# module_HC05.net
KiCad netlist of a schematic drawn in EAGLE
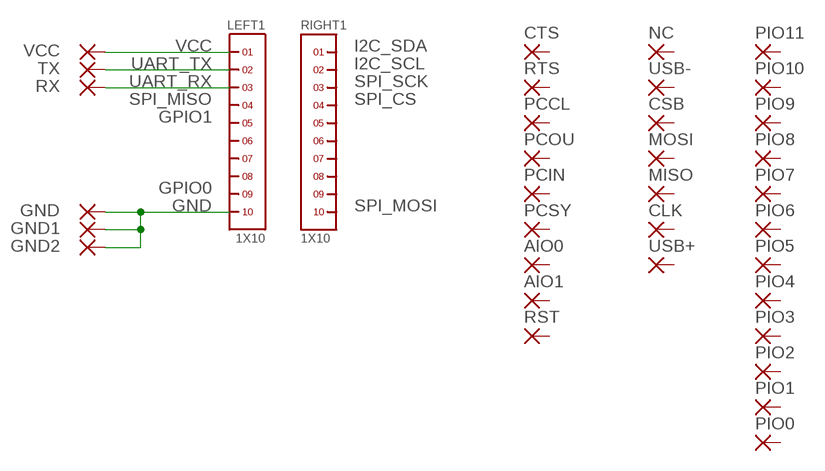
[diagram p0: schematic, sheet 1]

(export (version "E")
  (design (tool "Eeschema 10.0.6"))
  (components
    (comp (ref "AIO0")
      (value "SMD1")
      (footprint "eagle-import:SMD0,65-1,27")
      (libsource (lib "eagle-import") (part "SMD1"))
    )
    (comp (ref "AIO1")
      (value "SMD1")
      (footprint "eagle-import:SMD0,65-1,27")
      (libsource (lib "eagle-import") (part "SMD1"))
    )
    (comp (ref "CLK")
      (value "SMD1")
      (footprint "eagle-import:SMD0,65-1,27")
      (libsource (lib "eagle-import") (part "SMD1"))
    )
    (comp (ref "CSB")
      (value "SMD1")
      (footprint "eagle-import:SMD0,65-1,27")
      (libsource (lib "eagle-import") (part "SMD1"))
    )
    (comp (ref "CTS")
      (value "SMD1")
      (footprint "eagle-import:SMD0,65-1,27")
      (libsource (lib "eagle-import") (part "SMD1"))
    )
    (comp (ref "GND")
      (value "SMD1")
      (footprint "eagle-import:SMD0,65-1,27")
      (libsource (lib "eagle-import") (part "SMD1"))
    )
    (comp (ref "GND1")
      (value "SMD1")
      (footprint "eagle-import:SMD0,65-1,27")
      (libsource (lib "eagle-import") (part "SMD1"))
    )
    (comp (ref "GND2")
      (value "SMD1")
      (footprint "eagle-import:SMD0,65-1,27")
      (libsource (lib "eagle-import") (part "SMD1"))
    )
    (comp (ref "LEFT1")
      (value "1X10")
      (footprint "eagle-import:1X10")
      (libsource (lib "eagle-import") (part "1X10"))
    )
    (comp (ref "MISO")
      (value "SMD1")
      (footprint "eagle-import:SMD0,65-1,27")
      (libsource (lib "eagle-import") (part "SMD1"))
    )
    (comp (ref "MOSI")
      (value "SMD1")
      (footprint "eagle-import:SMD0,65-1,27")
      (libsource (lib "eagle-import") (part "SMD1"))
    )
    (comp (ref "NC")
      (value "SMD1")
      (footprint "eagle-import:SMD0,65-1,27")
      (libsource (lib "eagle-import") (part "SMD1"))
    )
    (comp (ref "PCCL")
      (value "SMD1")
      (footprint "eagle-import:SMD0,65-1,27")
      (libsource (lib "eagle-import") (part "SMD1"))
    )
    (comp (ref "PCIN")
      (value "SMD1")
      (footprint "eagle-import:SMD0,65-1,27")
      (libsource (lib "eagle-import") (part "SMD1"))
    )
    (comp (ref "PCOU")
      (value "SMD1")
      (footprint "eagle-import:SMD0,65-1,27")
      (libsource (lib "eagle-import") (part "SMD1"))
    )
    (comp (ref "PCSY")
      (value "SMD1")
      (footprint "eagle-import:SMD0,65-1,27")
      (libsource (lib "eagle-import") (part "SMD1"))
    )
    (comp (ref "PIO0")
      (value "SMD1")
      (footprint "eagle-import:SMD0,65-1,27")
      (libsource (lib "eagle-import") (part "SMD1"))
    )
    (comp (ref "PIO1")
      (value "SMD1")
      (footprint "eagle-import:SMD0,65-1,27")
      (libsource (lib "eagle-import") (part "SMD1"))
    )
    (comp (ref "PIO2")
      (value "SMD1")
      (footprint "eagle-import:SMD0,65-1,27")
      (libsource (lib "eagle-import") (part "SMD1"))
    )
    (comp (ref "PIO3")
      (value "SMD1")
      (footprint "eagle-import:SMD0,65-1,27")
      (libsource (lib "eagle-import") (part "SMD1"))
    )
    (comp (ref "PIO4")
      (value "SMD1")
      (footprint "eagle-import:SMD0,65-1,27")
      (libsource (lib "eagle-import") (part "SMD1"))
    )
    (comp (ref "PIO5")
      (value "SMD1")
      (footprint "eagle-import:SMD0,65-1,27")
      (libsource (lib "eagle-import") (part "SMD1"))
    )
    (comp (ref "PIO6")
      (value "SMD1")
      (footprint "eagle-import:SMD0,65-1,27")
      (libsource (lib "eagle-import") (part "SMD1"))
    )
    (comp (ref "PIO7")
      (value "SMD1")
      (footprint "eagle-import:SMD0,65-1,27")
      (libsource (lib "eagle-import") (part "SMD1"))
    )
    (comp (ref "PIO8")
      (value "SMD1")
      (footprint "eagle-import:SMD0,65-1,27")
      (libsource (lib "eagle-import") (part "SMD1"))
    )
    (comp (ref "PIO9")
      (value "SMD1")
      (footprint "eagle-import:SMD0,65-1,27")
      (libsource (lib "eagle-import") (part "SMD1"))
    )
    (comp (ref "PIO10")
      (value "SMD1")
      (footprint "eagle-import:SMD0,65-1,27")
      (libsource (lib "eagle-import") (part "SMD1"))
    )
    (comp (ref "PIO11")
      (value "SMD1")
      (footprint "eagle-import:SMD0,65-1,27")
      (libsource (lib "eagle-import") (part "SMD1"))
    )
    (comp (ref "RIGHT1")
      (value "1X10")
      (footprint "eagle-import:1X10")
      (libsource (lib "eagle-import") (part "1X10"))
    )
    (comp (ref "RST")
      (value "SMD1")
      (footprint "eagle-import:SMD0,65-1,27")
      (libsource (lib "eagle-import") (part "SMD1"))
    )
    (comp (ref "RTS")
      (value "SMD1")
      (footprint "eagle-import:SMD0,65-1,27")
      (libsource (lib "eagle-import") (part "SMD1"))
    )
    (comp (ref "RX")
      (value "SMD1")
      (footprint "eagle-import:SMD0,65-1,27")
      (libsource (lib "eagle-import") (part "SMD1"))
    )
    (comp (ref "TX")
      (value "SMD1")
      (footprint "eagle-import:SMD0,65-1,27")
      (libsource (lib "eagle-import") (part "SMD1"))
    )
    (comp (ref "USB+")
      (value "SMD1")
      (footprint "eagle-import:SMD0,65-1,27")
      (libsource (lib "eagle-import") (part "SMD1"))
    )
    (comp (ref "USB-")
      (value "SMD1")
      (footprint "eagle-import:SMD0,65-1,27")
      (libsource (lib "eagle-import") (part "SMD1"))
    )
    (comp (ref "VCC")
      (value "SMD1")
      (footprint "eagle-import:SMD0,65-1,27")
      (libsource (lib "eagle-import") (part "SMD1"))
    )
  )
  (nets
    (net (code "1") (name "Net-(GND-P)") (class "Default")
      (node (ref "GND") (pin "1") (pinfunction "P_1") (pintype "passive"))
      (node (ref "GND1") (pin "1") (pinfunction "P_1") (pintype "passive"))
      (node (ref "GND2") (pin "1") (pinfunction "P_1") (pintype "passive"))
      (node (ref "LEFT1") (pin "10") (pinfunction "10_10") (pintype "bidirectional"))
    )
    (net (code "2") (name "Net-(RX-P)") (class "Default")
      (node (ref "LEFT1") (pin "3") (pinfunction "3_3") (pintype "bidirectional"))
      (node (ref "RX") (pin "1") (pinfunction "P_1") (pintype "passive"))
    )
    (net (code "3") (name "Net-(TX-P)") (class "Default")
      (node (ref "LEFT1") (pin "2") (pinfunction "2_2") (pintype "bidirectional"))
      (node (ref "TX") (pin "1") (pinfunction "P_1") (pintype "passive"))
    )
    (net (code "4") (name "Net-(VCC-P)") (class "Default")
      (node (ref "LEFT1") (pin "1") (pinfunction "1_1") (pintype "bidirectional"))
      (node (ref "VCC") (pin "1") (pinfunction "P_1") (pintype "passive"))
    )
    (net (code "5") (name "unconnected-(AIO0-P-Pad1)") (class "Default")
      (node (ref "AIO0") (pin "1") (pinfunction "P_1") (pintype "passive"))
    )
    (net (code "6") (name "unconnected-(AIO1-P-Pad1)") (class "Default")
      (node (ref "AIO1") (pin "1") (pinfunction "P_1") (pintype "passive"))
    )
    (net (code "7") (name "unconnected-(CLK-P-Pad1)") (class "Default")
      (node (ref "CLK") (pin "1") (pinfunction "P_1") (pintype "passive"))
    )
    (net (code "8") (name "unconnected-(CSB-P-Pad1)") (class "Default")
      (node (ref "CSB") (pin "1") (pinfunction "P_1") (pintype "passive"))
    )
    (net (code "9") (name "unconnected-(CTS-P-Pad1)") (class "Default")
      (node (ref "CTS") (pin "1") (pinfunction "P_1") (pintype "passive"))
    )
    (net (code "10") (name "unconnected-(LEFT1-Pad4)") (class "Default")
      (node (ref "LEFT1") (pin "4") (pinfunction "4_4") (pintype "bidirectional"))
    )
    (net (code "11") (name "unconnected-(LEFT1-Pad5)") (class "Default")
      (node (ref "LEFT1") (pin "5") (pinfunction "5_5") (pintype "bidirectional"))
    )
    (net (code "12") (name "unconnected-(LEFT1-Pad6)") (class "Default")
      (node (ref "LEFT1") (pin "6") (pinfunction "6_6") (pintype "bidirectional"))
    )
    (net (code "13") (name "unconnected-(LEFT1-Pad7)") (class "Default")
      (node (ref "LEFT1") (pin "7") (pinfunction "7_7") (pintype "bidirectional"))
    )
    (net (code "14") (name "unconnected-(LEFT1-Pad8)") (class "Default")
      (node (ref "LEFT1") (pin "8") (pinfunction "8_8") (pintype "bidirectional"))
    )
    (net (code "15") (name "unconnected-(LEFT1-Pad9)") (class "Default")
      (node (ref "LEFT1") (pin "9") (pinfunction "9_9") (pintype "bidirectional"))
    )
    (net (code "16") (name "unconnected-(MISO-P-Pad1)") (class "Default")
      (node (ref "MISO") (pin "1") (pinfunction "P_1") (pintype "passive"))
    )
    (net (code "17") (name "unconnected-(MOSI-P-Pad1)") (class "Default")
      (node (ref "MOSI") (pin "1") (pinfunction "P_1") (pintype "passive"))
    )
    (net (code "18") (name "unconnected-(NC-P-Pad1)") (class "Default")
      (node (ref "NC") (pin "1") (pinfunction "P_1") (pintype "passive"))
    )
    (net (code "19") (name "unconnected-(PCCL-P-Pad1)") (class "Default")
      (node (ref "PCCL") (pin "1") (pinfunction "P_1") (pintype "passive"))
    )
    (net (code "20") (name "unconnected-(PCIN-P-Pad1)") (class "Default")
      (node (ref "PCIN") (pin "1") (pinfunction "P_1") (pintype "passive"))
    )
    (net (code "21") (name "unconnected-(PCOU-P-Pad1)") (class "Default")
      (node (ref "PCOU") (pin "1") (pinfunction "P_1") (pintype "passive"))
    )
    (net (code "22") (name "unconnected-(PCSY-P-Pad1)") (class "Default")
      (node (ref "PCSY") (pin "1") (pinfunction "P_1") (pintype "passive"))
    )
    (net (code "23") (name "unconnected-(PIO0-P-Pad1)") (class "Default")
      (node (ref "PIO0") (pin "1") (pinfunction "P_1") (pintype "passive"))
    )
    (net (code "24") (name "unconnected-(PIO1-P-Pad1)") (class "Default")
      (node (ref "PIO1") (pin "1") (pinfunction "P_1") (pintype "passive"))
    )
    (net (code "25") (name "unconnected-(PIO2-P-Pad1)") (class "Default")
      (node (ref "PIO2") (pin "1") (pinfunction "P_1") (pintype "passive"))
    )
    (net (code "26") (name "unconnected-(PIO3-P-Pad1)") (class "Default")
      (node (ref "PIO3") (pin "1") (pinfunction "P_1") (pintype "passive"))
    )
    (net (code "27") (name "unconnected-(PIO4-P-Pad1)") (class "Default")
      (node (ref "PIO4") (pin "1") (pinfunction "P_1") (pintype "passive"))
    )
    (net (code "28") (name "unconnected-(PIO5-P-Pad1)") (class "Default")
      (node (ref "PIO5") (pin "1") (pinfunction "P_1") (pintype "passive"))
    )
    (net (code "29") (name "unconnected-(PIO6-P-Pad1)") (class "Default")
      (node (ref "PIO6") (pin "1") (pinfunction "P_1") (pintype "passive"))
    )
    (net (code "30") (name "unconnected-(PIO7-P-Pad1)") (class "Default")
      (node (ref "PIO7") (pin "1") (pinfunction "P_1") (pintype "passive"))
    )
    (net (code "31") (name "unconnected-(PIO8-P-Pad1)") (class "Default")
      (node (ref "PIO8") (pin "1") (pinfunction "P_1") (pintype "passive"))
    )
    (net (code "32") (name "unconnected-(PIO9-P-Pad1)") (class "Default")
      (node (ref "PIO9") (pin "1") (pinfunction "P_1") (pintype "passive"))
    )
    (net (code "33") (name "unconnected-(PIO10-P-Pad1)") (class "Default")
      (node (ref "PIO10") (pin "1") (pinfunction "P_1") (pintype "passive"))
    )
    (net (code "34") (name "unconnected-(PIO11-P-Pad1)") (class "Default")
      (node (ref "PIO11") (pin "1") (pinfunction "P_1") (pintype "passive"))
    )
    (net (code "35") (name "unconnected-(RIGHT1-Pad1)") (class "Default")
      (node (ref "RIGHT1") (pin "1") (pinfunction "1_1") (pintype "bidirectional"))
    )
    (net (code "36") (name "unconnected-(RIGHT1-Pad2)") (class "Default")
      (node (ref "RIGHT1") (pin "2") (pinfunction "2_2") (pintype "bidirectional"))
    )
    (net (code "37") (name "unconnected-(RIGHT1-Pad3)") (class "Default")
      (node (ref "RIGHT1") (pin "3") (pinfunction "3_3") (pintype "bidirectional"))
    )
    (net (code "38") (name "unconnected-(RIGHT1-Pad4)") (class "Default")
      (node (ref "RIGHT1") (pin "4") (pinfunction "4_4") (pintype "bidirectional"))
    )
    (net (code "39") (name "unconnected-(RIGHT1-Pad5)") (class "Default")
      (node (ref "RIGHT1") (pin "5") (pinfunction "5_5") (pintype "bidirectional"))
    )
    (net (code "40") (name "unconnected-(RIGHT1-Pad6)") (class "Default")
      (node (ref "RIGHT1") (pin "6") (pinfunction "6_6") (pintype "bidirectional"))
    )
    (net (code "41") (name "unconnected-(RIGHT1-Pad7)") (class "Default")
      (node (ref "RIGHT1") (pin "7") (pinfunction "7_7") (pintype "bidirectional"))
    )
    (net (code "42") (name "unconnected-(RIGHT1-Pad8)") (class "Default")
      (node (ref "RIGHT1") (pin "8") (pinfunction "8_8") (pintype "bidirectional"))
    )
    (net (code "43") (name "unconnected-(RIGHT1-Pad9)") (class "Default")
      (node (ref "RIGHT1") (pin "9") (pinfunction "9_9") (pintype "bidirectional"))
    )
    (net (code "44") (name "unconnected-(RIGHT1-Pad10)") (class "Default")
      (node (ref "RIGHT1") (pin "10") (pinfunction "10_10") (pintype "bidirectional"))
    )
    (net (code "45") (name "unconnected-(RST-P-Pad1)") (class "Default")
      (node (ref "RST") (pin "1") (pinfunction "P_1") (pintype "passive"))
    )
    (net (code "46") (name "unconnected-(RTS-P-Pad1)") (class "Default")
      (node (ref "RTS") (pin "1") (pinfunction "P_1") (pintype "passive"))
    )
    (net (code "47") (name "unconnected-(USB+-P-Pad1)") (class "Default")
      (node (ref "USB+") (pin "1") (pinfunction "P_1") (pintype "passive"))
    )
    (net (code "48") (name "unconnected-(USB--P-Pad1)") (class "Default")
      (node (ref "USB-") (pin "1") (pinfunction "P_1") (pintype "passive"))
    )
  )
)
